# I2C_Multiplexer.net
KiCad netlist of a schematic drawn in Altium Designer
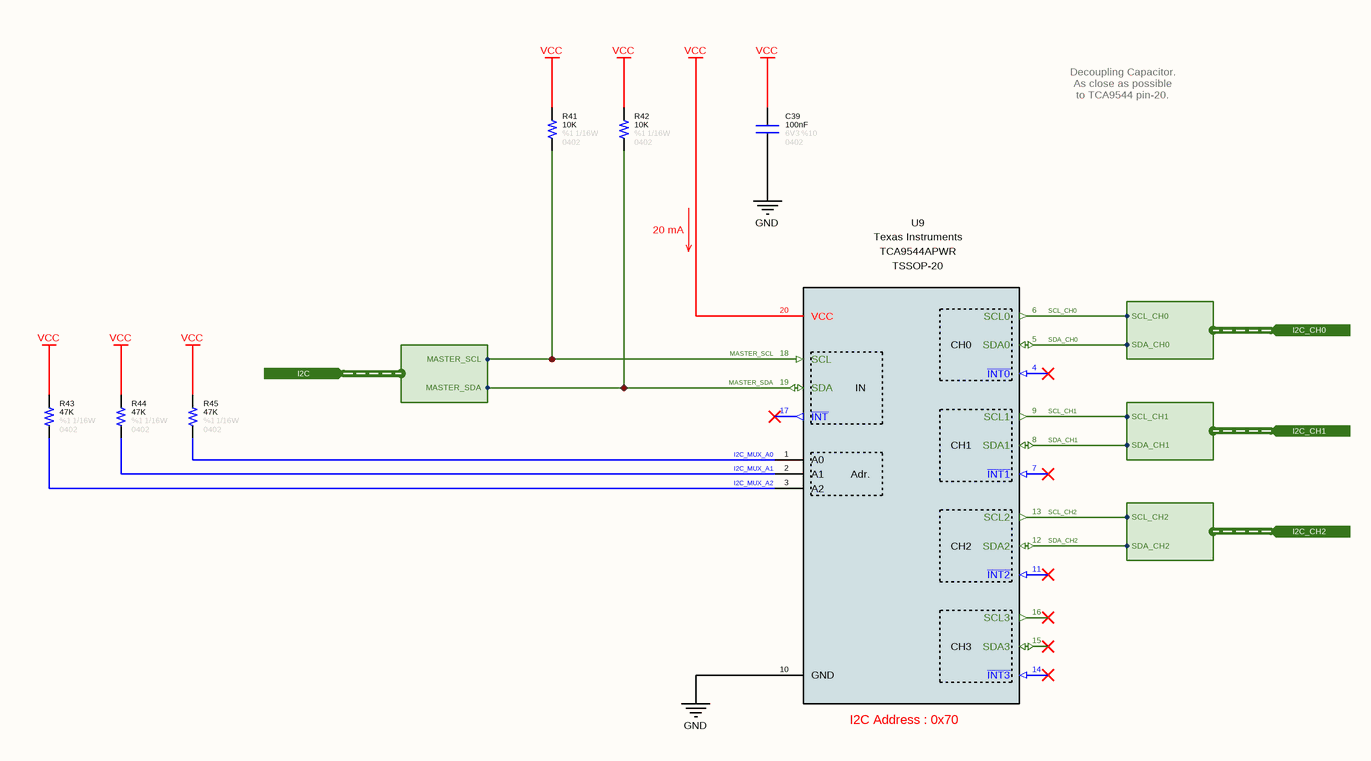
[diagram p0: I2C Multiplexer.SchDoc]

(export (version "E")
  (design (tool "Eeschema 10.0.6"))
  (components
    (comp (ref "C39")
      (value "100nF")
      (footprint "CAPACITOR_0402")
      (description "Capacitor - 100nF [0402-6V3] (Ceramic)")
      (fields
        (field (name "MANUFACTURER PART NUMBER") "04026D104KAT4A")
        (field (name "TOLERANCE") "%10")
        (field (name "VOLTAGE") "6V3")
        (field (name "CASE") "0402")
        (field (name "Comment") "Capacitor - 100nF [0402] (Ceramic)")
      )
      (libsource (lib "P101DA_Library") (part "Capacitor - 100nF [0402-6V3]"))
    )
    (comp (ref "R41")
      (value "10K")
      (footprint "RESISTOR_0402")
      (description "Thick Film Resistors - SMD 1/16 W 10 KOhm 1%")
      (fields
        (field (name "MANUFACTURER PART NUMBER") "CRCW040210K0FKED")
        (field (name "TOLERANCE") "%1")
        (field (name "CASE") "0402")
        (field (name "POWER") "1/16W")
        (field (name "Comment") "10K - 0402 - %1 - 1/16W")
      )
      (libsource (lib "P101DA_Library") (part "Resistor - 10K [0402]"))
    )
    (comp (ref "R42")
      (value "10K")
      (footprint "RESISTOR_0402")
      (description "Thick Film Resistors - SMD 1/16 W 10 KOhm 1%")
      (fields
        (field (name "MANUFACTURER PART NUMBER") "CRCW040210K0FKED")
        (field (name "TOLERANCE") "%1")
        (field (name "CASE") "0402")
        (field (name "POWER") "1/16W")
        (field (name "Comment") "10K - 0402 - %1 - 1/16W")
      )
      (libsource (lib "P101DA_Library") (part "Resistor - 10K [0402]"))
    )
    (comp (ref "R43")
      (value "47K")
      (footprint "RESISTOR_0402")
      (description "Thick Film Resistors - SMD 1/16 W 47 KOhm 1%")
      (fields
        (field (name "MANUFACTURER PART NUMBER") "CRCW040247K0FKED")
        (field (name "TOLERANCE") "%1")
        (field (name "CASE") "0402")
        (field (name "POWER") "1/16W")
        (field (name "Comment") "47K - 0402 - %1 - 1/16W")
      )
      (libsource (lib "P101DA_Library") (part "Resistor - 47K [0402]"))
    )
    (comp (ref "R44")
      (value "47K")
      (footprint "RESISTOR_0402")
      (description "Thick Film Resistors - SMD 1/16 W 47 KOhm 1%")
      (fields
        (field (name "MANUFACTURER PART NUMBER") "CRCW040247K0FKED")
        (field (name "TOLERANCE") "%1")
        (field (name "CASE") "0402")
        (field (name "POWER") "1/16W")
        (field (name "Comment") "47K - 0402 - %1 - 1/16W")
      )
      (libsource (lib "P101DA_Library") (part "Resistor - 47K [0402]"))
    )
    (comp (ref "R45")
      (value "47K")
      (footprint "RESISTOR_0402")
      (description "Thick Film Resistors - SMD 1/16 W 47 KOhm 1%")
      (fields
        (field (name "MANUFACTURER PART NUMBER") "CRCW040247K0FKED")
        (field (name "TOLERANCE") "%1")
        (field (name "CASE") "0402")
        (field (name "POWER") "1/16W")
        (field (name "Comment") "47K - 0402 - %1 - 1/16W")
      )
      (libsource (lib "P101DA_Library") (part "Resistor - 47K [0402]"))
    )
    (comp (ref "U9")
      (value "TCA9548APWR")
      (footprint "TSSOP-20")
      (description "TEXAS INSTRUMENTS - TCA9548APWR - I2C SWITCH W/ RESET, 8-CH, TSSOP-24")
      (fields
        (field (name "MANUFACTURER NAME") "Texas Instruments")
        (field (name "MANUFACTURER PART NUMBER") "TCA9544APWR")
        (field (name "CASE") "TSSOP-20")
      )
      (libsource (lib "P101DA_Library") (part "IC - TCA9544A"))
    )
  )
  (nets
    (net (code "5") (name "/I2C_MUX_A0") (class "Default")
      (node (ref "R45") (pin "1") (pinfunction "1_1") (pintype "passive"))
      (node (ref "U9") (pin "1") (pinfunction "A0_1") (pintype "passive"))
    )
    (net (code "6") (name "/I2C_MUX_A1") (class "Default")
      (node (ref "R44") (pin "1") (pinfunction "1_1") (pintype "passive"))
      (node (ref "U9") (pin "2") (pinfunction "A1_2") (pintype "passive"))
    )
    (net (code "7") (name "/I2C_MUX_A2") (class "Default")
      (node (ref "R43") (pin "1") (pinfunction "1_1") (pintype "passive"))
      (node (ref "U9") (pin "3") (pinfunction "A2_3") (pintype "passive"))
    )
    (net (code "8") (name "/MASTER_SCL") (class "Default")
      (node (ref "R41") (pin "1") (pinfunction "1_1") (pintype "passive"))
      (node (ref "U9") (pin "18") (pinfunction "SCL_18") (pintype "input"))
    )
    (net (code "9") (name "/MASTER_SDA") (class "Default")
      (node (ref "R42") (pin "1") (pinfunction "1_1") (pintype "passive"))
      (node (ref "U9") (pin "19") (pinfunction "SDA_19") (pintype "bidirectional"))
    )
    (net (code "10") (name "/SCL_CH0") (class "Default")
      (node (ref "U9") (pin "6") (pinfunction "SCL0_6") (pintype "output"))
    )
    (net (code "11") (name "/SCL_CH1") (class "Default")
      (node (ref "U9") (pin "9") (pinfunction "SCL1_9") (pintype "output"))
    )
    (net (code "12") (name "/SCL_CH2") (class "Default")
      (node (ref "U9") (pin "13") (pinfunction "SCL2_13") (pintype "output"))
    )
    (net (code "13") (name "/SDA_CH0") (class "Default")
      (node (ref "U9") (pin "5") (pinfunction "SDA0_5") (pintype "bidirectional"))
    )
    (net (code "14") (name "/SDA_CH1") (class "Default")
      (node (ref "U9") (pin "8") (pinfunction "SDA1_8") (pintype "bidirectional"))
    )
    (net (code "15") (name "/SDA_CH2") (class "Default")
      (node (ref "U9") (pin "12") (pinfunction "SDA2_12") (pintype "bidirectional"))
    )
    (net (code "20") (name "GND") (class "Default")
      (node (ref "C39") (pin "1") (pinfunction "1_1") (pintype "passive"))
      (node (ref "U9") (pin "10") (pinfunction "GND_10") (pintype "power_in"))
    )
    (net (code "21") (name "VCC") (class "Default")
      (node (ref "C39") (pin "2") (pinfunction "2_2") (pintype "passive"))
      (node (ref "R41") (pin "2") (pinfunction "2_2") (pintype "passive"))
      (node (ref "R42") (pin "2") (pinfunction "2_2") (pintype "passive"))
      (node (ref "R43") (pin "2") (pinfunction "2_2") (pintype "passive"))
      (node (ref "R44") (pin "2") (pinfunction "2_2") (pintype "passive"))
      (node (ref "R45") (pin "2") (pinfunction "2_2") (pintype "passive"))
      (node (ref "U9") (pin "20") (pinfunction "VCC_20") (pintype "power_in"))
    )
    (net (code "22") (name "unconnected-(U9-SCL3-Pad16)") (class "Default")
      (node (ref "U9") (pin "16") (pinfunction "SCL3_16") (pintype "output+no_connect"))
    )
    (net (code "23") (name "unconnected-(U9-SDA3-Pad15)") (class "Default")
      (node (ref "U9") (pin "15") (pinfunction "SDA3_15") (pintype "bidirectional+no_connect"))
    )
    (net (code "24") (name "unconnected-(U9-~{INT0}-Pad4)") (class "Default")
      (node (ref "U9") (pin "4") (pinfunction "~{INT0}_4") (pintype "input+no_connect"))
    )
    (net (code "25") (name "unconnected-(U9-~{INT1}-Pad7)") (class "Default")
      (node (ref "U9") (pin "7") (pinfunction "~{INT1}_7") (pintype "input+no_connect"))
    )
    (net (code "26") (name "unconnected-(U9-~{INT2}-Pad11)") (class "Default")
      (node (ref "U9") (pin "11") (pinfunction "~{INT2}_11") (pintype "input+no_connect"))
    )
    (net (code "27") (name "unconnected-(U9-~{INT3}-Pad14)") (class "Default")
      (node (ref "U9") (pin "14") (pinfunction "~{INT3}_14") (pintype "input+no_connect"))
    )
    (net (code "28") (name "unconnected-(U9-~{INT}-Pad17)") (class "Default")
      (node (ref "U9") (pin "17") (pinfunction "~{INT}_17") (pintype "output+no_connect"))
    )
  )
)
